# board_d-01-buttons.net
KiCad netlist of a schematic drawn in EAGLE
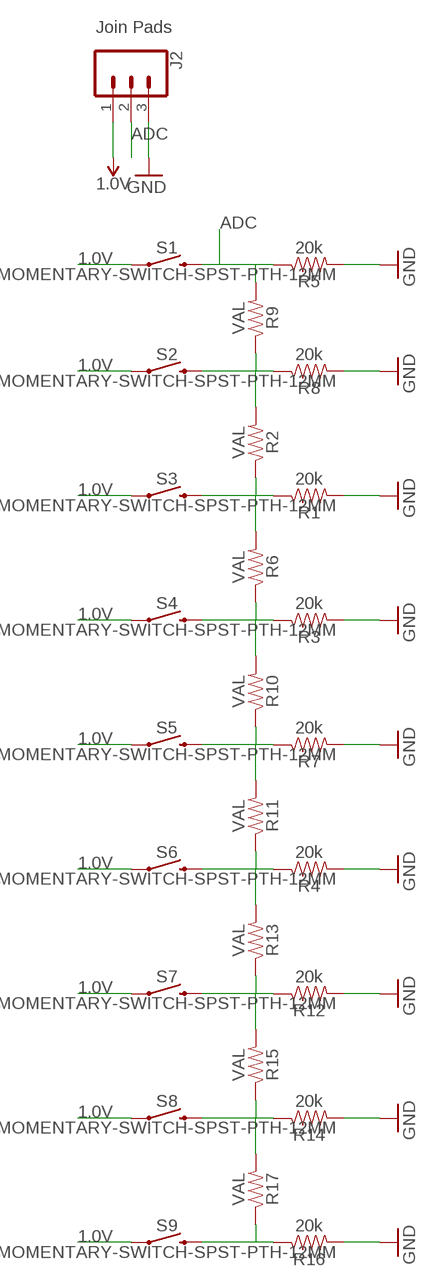
[diagram p0: schematic, sheet 1]

(export (version "E")
  (design (tool "Eeschema 10.0.6"))
  (components
    (comp (ref "J2")
      (value "CONN_03LOCK_LONGPADS")
      (footprint "eagle-import:1X03_LOCK_LONGPADS")
      (libsource (lib "eagle-import") (part "CONN_03LOCK_LONGPADS"))
    )
    (comp (ref "R1")
      (value "20k")
      (footprint "eagle-import:AXIAL-0.3")
      (libsource (lib "eagle-import") (part "1KOHM-HORIZ-1/4W-1%"))
    )
    (comp (ref "R2")
      (value "VAL")
      (footprint "eagle-import:AXIAL-0.3")
      (libsource (lib "eagle-import") (part "1KOHM-HORIZ-1/4W-1%"))
    )
    (comp (ref "R3")
      (value "20k")
      (footprint "eagle-import:AXIAL-0.3")
      (libsource (lib "eagle-import") (part "1KOHM-HORIZ-1/4W-1%"))
    )
    (comp (ref "R4")
      (value "20k")
      (footprint "eagle-import:AXIAL-0.3")
      (libsource (lib "eagle-import") (part "1KOHM-HORIZ-1/4W-1%"))
    )
    (comp (ref "R5")
      (value "20k")
      (footprint "eagle-import:AXIAL-0.3")
      (libsource (lib "eagle-import") (part "1KOHM-HORIZ-1/4W-1%"))
    )
    (comp (ref "R6")
      (value "VAL")
      (footprint "eagle-import:AXIAL-0.3")
      (libsource (lib "eagle-import") (part "1KOHM-HORIZ-1/4W-1%"))
    )
    (comp (ref "R7")
      (value "20k")
      (footprint "eagle-import:AXIAL-0.3")
      (libsource (lib "eagle-import") (part "1KOHM-HORIZ-1/4W-1%"))
    )
    (comp (ref "R8")
      (value "20k")
      (footprint "eagle-import:AXIAL-0.3")
      (libsource (lib "eagle-import") (part "1KOHM-HORIZ-1/4W-1%"))
    )
    (comp (ref "R9")
      (value "VAL")
      (footprint "eagle-import:AXIAL-0.3")
      (libsource (lib "eagle-import") (part "1KOHM-HORIZ-1/4W-1%"))
    )
    (comp (ref "R10")
      (value "VAL")
      (footprint "eagle-import:AXIAL-0.3")
      (libsource (lib "eagle-import") (part "1KOHM-HORIZ-1/4W-1%"))
    )
    (comp (ref "R11")
      (value "VAL")
      (footprint "eagle-import:AXIAL-0.3")
      (libsource (lib "eagle-import") (part "1KOHM-HORIZ-1/4W-1%"))
    )
    (comp (ref "R12")
      (value "20k")
      (footprint "eagle-import:AXIAL-0.3")
      (libsource (lib "eagle-import") (part "1KOHM-HORIZ-1/4W-1%"))
    )
    (comp (ref "R13")
      (value "VAL")
      (footprint "eagle-import:AXIAL-0.3")
      (libsource (lib "eagle-import") (part "1KOHM-HORIZ-1/4W-1%"))
    )
    (comp (ref "R14")
      (value "20k")
      (footprint "eagle-import:AXIAL-0.3")
      (libsource (lib "eagle-import") (part "1KOHM-HORIZ-1/4W-1%"))
    )
    (comp (ref "R15")
      (value "VAL")
      (footprint "eagle-import:AXIAL-0.3")
      (libsource (lib "eagle-import") (part "1KOHM-HORIZ-1/4W-1%"))
    )
    (comp (ref "R16")
      (value "20k")
      (footprint "eagle-import:AXIAL-0.3")
      (libsource (lib "eagle-import") (part "1KOHM-HORIZ-1/4W-1%"))
    )
    (comp (ref "R17")
      (value "VAL")
      (footprint "eagle-import:AXIAL-0.3")
      (libsource (lib "eagle-import") (part "1KOHM-HORIZ-1/4W-1%"))
    )
    (comp (ref "S1")
      (value "MOMENTARY-SWITCH-SPST-PTH-12MM")
      (footprint "eagle-import:TACTILE_SWITCH_PTH_12MM")
      (libsource (lib "eagle-import") (part "MOMENTARY-SWITCH-SPST-PTH-12MM"))
    )
    (comp (ref "S2")
      (value "MOMENTARY-SWITCH-SPST-PTH-12MM")
      (footprint "eagle-import:TACTILE_SWITCH_PTH_12MM")
      (libsource (lib "eagle-import") (part "MOMENTARY-SWITCH-SPST-PTH-12MM"))
    )
    (comp (ref "S3")
      (value "MOMENTARY-SWITCH-SPST-PTH-12MM")
      (footprint "eagle-import:TACTILE_SWITCH_PTH_12MM")
      (libsource (lib "eagle-import") (part "MOMENTARY-SWITCH-SPST-PTH-12MM"))
    )
    (comp (ref "S4")
      (value "MOMENTARY-SWITCH-SPST-PTH-12MM")
      (footprint "eagle-import:TACTILE_SWITCH_PTH_12MM")
      (libsource (lib "eagle-import") (part "MOMENTARY-SWITCH-SPST-PTH-12MM"))
    )
    (comp (ref "S5")
      (value "MOMENTARY-SWITCH-SPST-PTH-12MM")
      (footprint "eagle-import:TACTILE_SWITCH_PTH_12MM")
      (libsource (lib "eagle-import") (part "MOMENTARY-SWITCH-SPST-PTH-12MM"))
    )
    (comp (ref "S6")
      (value "MOMENTARY-SWITCH-SPST-PTH-12MM")
      (footprint "eagle-import:TACTILE_SWITCH_PTH_12MM")
      (libsource (lib "eagle-import") (part "MOMENTARY-SWITCH-SPST-PTH-12MM"))
    )
    (comp (ref "S7")
      (value "MOMENTARY-SWITCH-SPST-PTH-12MM")
      (footprint "eagle-import:TACTILE_SWITCH_PTH_12MM")
      (libsource (lib "eagle-import") (part "MOMENTARY-SWITCH-SPST-PTH-12MM"))
    )
    (comp (ref "S8")
      (value "MOMENTARY-SWITCH-SPST-PTH-12MM")
      (footprint "eagle-import:TACTILE_SWITCH_PTH_12MM")
      (libsource (lib "eagle-import") (part "MOMENTARY-SWITCH-SPST-PTH-12MM"))
    )
    (comp (ref "S9")
      (value "MOMENTARY-SWITCH-SPST-PTH-12MM")
      (footprint "eagle-import:TACTILE_SWITCH_PTH_12MM")
      (libsource (lib "eagle-import") (part "MOMENTARY-SWITCH-SPST-PTH-12MM"))
    )
  )
  (nets
    (net (code "1") (name "/ADC") (class "Default")
      (node (ref "J2") (pin "2") (pinfunction "2_2") (pintype "passive"))
      (node (ref "R5") (pin "P$1") (pinfunction "1_P$1") (pintype "passive"))
      (node (ref "R9") (pin "P$2") (pinfunction "2_P$2") (pintype "passive"))
      (node (ref "S1") (pin "3") (pinfunction "2_3") (pintype "passive"))
    )
    (net (code "2") (name "1.0V") (class "Default")
      (node (ref "J2") (pin "1") (pinfunction "1_1") (pintype "passive"))
      (node (ref "S1") (pin "1") (pinfunction "1_1") (pintype "passive"))
      (node (ref "S2") (pin "1") (pinfunction "1_1") (pintype "passive"))
      (node (ref "S3") (pin "1") (pinfunction "1_1") (pintype "passive"))
      (node (ref "S4") (pin "1") (pinfunction "1_1") (pintype "passive"))
      (node (ref "S5") (pin "1") (pinfunction "1_1") (pintype "passive"))
      (node (ref "S6") (pin "1") (pinfunction "1_1") (pintype "passive"))
      (node (ref "S7") (pin "1") (pinfunction "1_1") (pintype "passive"))
      (node (ref "S8") (pin "1") (pinfunction "1_1") (pintype "passive"))
      (node (ref "S9") (pin "1") (pinfunction "1_1") (pintype "passive"))
    )
    (net (code "3") (name "GND") (class "Default")
      (node (ref "J2") (pin "3") (pinfunction "3_3") (pintype "passive"))
      (node (ref "R1") (pin "P$2") (pinfunction "2_P$2") (pintype "passive"))
      (node (ref "R12") (pin "P$2") (pinfunction "2_P$2") (pintype "passive"))
      (node (ref "R14") (pin "P$2") (pinfunction "2_P$2") (pintype "passive"))
      (node (ref "R16") (pin "P$2") (pinfunction "2_P$2") (pintype "passive"))
      (node (ref "R3") (pin "P$2") (pinfunction "2_P$2") (pintype "passive"))
      (node (ref "R4") (pin "P$2") (pinfunction "2_P$2") (pintype "passive"))
      (node (ref "R5") (pin "P$2") (pinfunction "2_P$2") (pintype "passive"))
      (node (ref "R7") (pin "P$2") (pinfunction "2_P$2") (pintype "passive"))
      (node (ref "R8") (pin "P$2") (pinfunction "2_P$2") (pintype "passive"))
    )
    (net (code "4") (name "Net-(R1-1)") (class "Default")
      (node (ref "R1") (pin "P$1") (pinfunction "1_P$1") (pintype "passive"))
      (node (ref "R2") (pin "P$1") (pinfunction "1_P$1") (pintype "passive"))
      (node (ref "R6") (pin "P$2") (pinfunction "2_P$2") (pintype "passive"))
      (node (ref "S3") (pin "3") (pinfunction "2_3") (pintype "passive"))
    )
    (net (code "5") (name "Net-(R2-2)") (class "Default")
      (node (ref "R2") (pin "P$2") (pinfunction "2_P$2") (pintype "passive"))
      (node (ref "R8") (pin "P$1") (pinfunction "1_P$1") (pintype "passive"))
      (node (ref "R9") (pin "P$1") (pinfunction "1_P$1") (pintype "passive"))
      (node (ref "S2") (pin "3") (pinfunction "2_3") (pintype "passive"))
    )
    (net (code "6") (name "Net-(R10-1)") (class "Default")
      (node (ref "R10") (pin "P$1") (pinfunction "1_P$1") (pintype "passive"))
      (node (ref "R11") (pin "P$2") (pinfunction "2_P$2") (pintype "passive"))
      (node (ref "R7") (pin "P$1") (pinfunction "1_P$1") (pintype "passive"))
      (node (ref "S5") (pin "3") (pinfunction "2_3") (pintype "passive"))
    )
    (net (code "7") (name "Net-(R10-2)") (class "Default")
      (node (ref "R10") (pin "P$2") (pinfunction "2_P$2") (pintype "passive"))
      (node (ref "R3") (pin "P$1") (pinfunction "1_P$1") (pintype "passive"))
      (node (ref "R6") (pin "P$1") (pinfunction "1_P$1") (pintype "passive"))
      (node (ref "S4") (pin "3") (pinfunction "2_3") (pintype "passive"))
    )
    (net (code "8") (name "Net-(R11-1)") (class "Default")
      (node (ref "R11") (pin "P$1") (pinfunction "1_P$1") (pintype "passive"))
      (node (ref "R13") (pin "P$2") (pinfunction "2_P$2") (pintype "passive"))
      (node (ref "R4") (pin "P$1") (pinfunction "1_P$1") (pintype "passive"))
      (node (ref "S6") (pin "3") (pinfunction "2_3") (pintype "passive"))
    )
    (net (code "9") (name "Net-(R12-1)") (class "Default")
      (node (ref "R12") (pin "P$1") (pinfunction "1_P$1") (pintype "passive"))
      (node (ref "R13") (pin "P$1") (pinfunction "1_P$1") (pintype "passive"))
      (node (ref "R15") (pin "P$2") (pinfunction "2_P$2") (pintype "passive"))
      (node (ref "S7") (pin "3") (pinfunction "2_3") (pintype "passive"))
    )
    (net (code "10") (name "Net-(R14-1)") (class "Default")
      (node (ref "R14") (pin "P$1") (pinfunction "1_P$1") (pintype "passive"))
      (node (ref "R15") (pin "P$1") (pinfunction "1_P$1") (pintype "passive"))
      (node (ref "R17") (pin "P$2") (pinfunction "2_P$2") (pintype "passive"))
      (node (ref "S8") (pin "3") (pinfunction "2_3") (pintype "passive"))
    )
    (net (code "11") (name "Net-(R16-1)") (class "Default")
      (node (ref "R16") (pin "P$1") (pinfunction "1_P$1") (pintype "passive"))
      (node (ref "R17") (pin "P$1") (pinfunction "1_P$1") (pintype "passive"))
      (node (ref "S9") (pin "3") (pinfunction "2_3") (pintype "passive"))
    )
  )
)
